# USB-C_Connector.net
KiCad netlist of a schematic drawn in Altium Designer
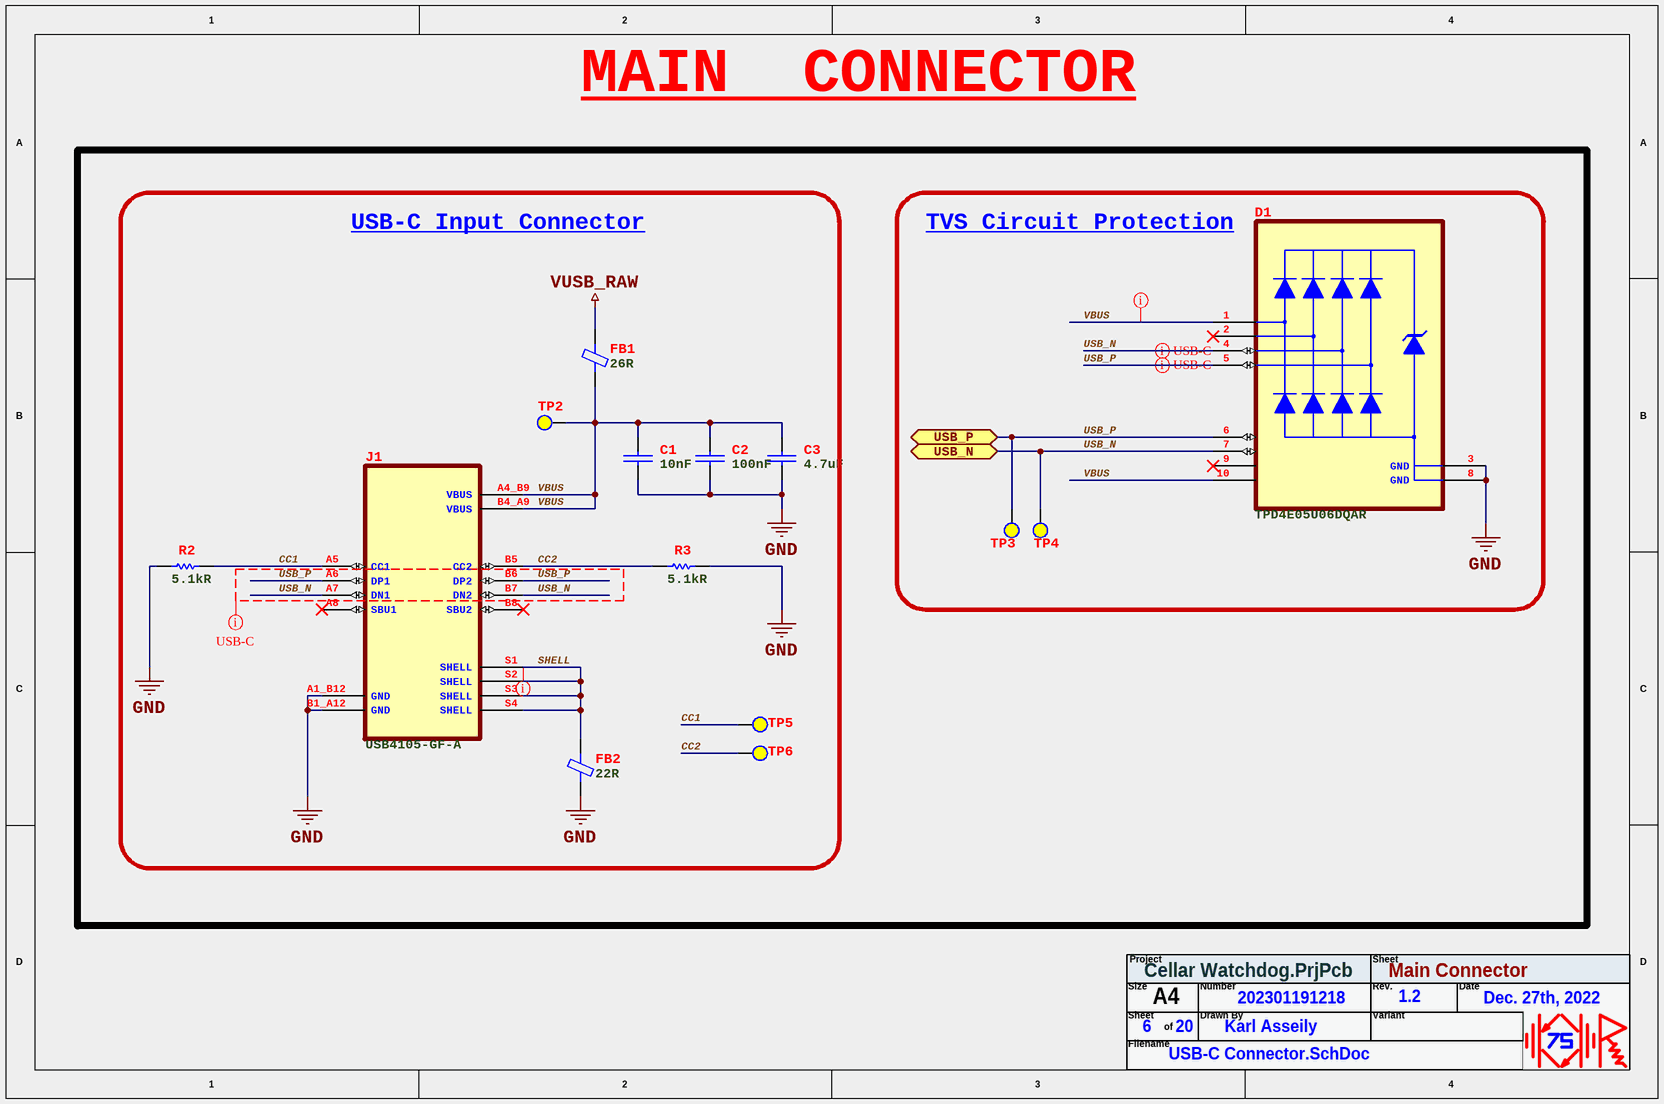
[diagram p0: USB-C Connector.SchDoc]

(export (version "E")
  (design (tool "Eeschema 10.0.6"))
  (components
    (comp (ref "C1")
      (value "10nF")
      (footprint "CAP_0603")
      (description "10000 pF ±10% 50V Ceramic Capacitor X7R 0603 (1608 Metric)")
      (fields
        (field (name "MANUFACTURER") "Yageo")
        (field (name "MANUFACTURER PART NUMBER") "CC0603KRX7R9BB103")
      )
      (libsource (lib "Cellar Watchdog") (part "CAP_10nF-50V-10%_0603"))
    )
    (comp (ref "C2")
      (value "100nF")
      (footprint "CAP_0603")
      (description "0.1 µF ±10% 50V Ceramic Capacitor X7R 0603 (1608 Metric)")
      (fields
        (field (name "MANUFACTURER") "Yageo")
        (field (name "MANUFACTURER PART NUMBER") "CC0603KRX7R9BB104")
      )
      (libsource (lib "Cellar Watchdog") (part "CAP_0.1uF-50V-10%_0603"))
    )
    (comp (ref "C3")
      (value "4.7uF")
      (footprint "CAP_0805")
      (description "4.7 µF ±10% 25V Ceramic Capacitor X7R 0805 (2012 Metric)")
      (fields
        (field (name "MANUFACTURER") "Yageo")
        (field (name "MANUFACTURER PART NUMBER") "CC0805KKX7R8BB475")
      )
      (libsource (lib "Cellar Watchdog") (part "CAP_4.7uF-25V-10%_0805"))
    )
    (comp (ref "D1")
      (value "TPD4E05U06DQAR")
      (footprint "DIO-T-A_10-USON")
      (description "14V Clamp 2.5A (8/20µs) Ipp Tvs Diode Surface Mount 10-USON (2.5x1)")
      (fields (field (name "MANUFACTURER") "Texas Instruments"))
      (libsource (lib "Cellar Watchdog") (part "DIO-T-A-UNI_6V-14V-2.5A_10-USON"))
    )
    (comp (ref "FB1")
      (value "26R")
      (footprint "FB_0603")
      (description "26 Ohms @ 100 MHz 1 Power Line Ferrite Bead 0603 (1608 Metric) 6A 7mOhm")
      (fields
        (field (name "MANUFACTURER") "Murata")
        (field (name "MANUFACTURER PART NUMBER") "BLM18SG260TZ1D")
      )
      (libsource (lib "Cellar Watchdog") (part "FB_26R-100MHz-6A_0603"))
    )
    (comp (ref "FB2")
      (value "22R")
      (footprint "FB_0603")
      (description "22 Ohms @ 100 MHz 1 Signal Line Ferrite Bead 0603 (1608 Metric) 500mA 350mOhm")
      (fields
        (field (name "MANUFACTURER") "Murata")
        (field (name "MANUFACTURER PART NUMBER") "BLM18BA220SN1D")
      )
      (libsource (lib "Cellar Watchdog") (part "FB_22R-100MHz-500mA_0603"))
    )
    (comp (ref "J1")
      (value "USB4105-GF-A")
      (footprint "CON-RCPT_USB2.0-Type-C_GCT_USB4105-GF-A")
      (fields (field (name "MANUFACTURER") "Global Connector Technology"))
      (libsource (lib "Cellar Watchdog") (part "CON-RCPT_USB2.0-Type-C_USB4105-GF-A"))
    )
    (comp (ref "R2")
      (value "5.1kR")
      (footprint "RES_0603")
      (description "5.1 kOhms ±1% 0.1W, 1/10W Chip Resistor 0603 (1608 Metric) Moisture Resistant Thick Film")
      (fields
        (field (name "MANUFACTURER") "Yageo")
        (field (name "MANUFACTURER PART NUMBER") "RC0603FR-075K1L")
      )
      (libsource (lib "Cellar Watchdog") (part "RES_5.1kR-100mW-1%_0603"))
    )
    (comp (ref "R3")
      (value "5.1kR")
      (footprint "RES_0603")
      (description "5.1 kOhms ±1% 0.1W, 1/10W Chip Resistor 0603 (1608 Metric) Moisture Resistant Thick Film")
      (fields
        (field (name "MANUFACTURER") "Yageo")
        (field (name "MANUFACTURER PART NUMBER") "RC0603FR-075K1L")
      )
      (libsource (lib "Cellar Watchdog") (part "RES_5.1kR-100mW-1%_0603"))
    )
    (comp (ref "TP2")
      (value "VBUS")
      (footprint "TEST POINT HOLE")
      (description "PCB Test Point")
      (libsource (lib "Cellar Watchdog") (part "Test Point"))
    )
    (comp (ref "TP3")
      (value "USB_P")
      (footprint "TEST POINT PAD")
      (description "PCB Test Point")
      (libsource (lib "Cellar Watchdog") (part "Test Point"))
    )
    (comp (ref "TP4")
      (value "USB_N")
      (footprint "TEST POINT PAD")
      (description "PCB Test Point")
      (libsource (lib "Cellar Watchdog") (part "Test Point"))
    )
    (comp (ref "TP5")
      (value "CC1")
      (footprint "TEST POINT PAD")
      (description "PCB Test Point")
      (libsource (lib "Cellar Watchdog") (part "Test Point"))
    )
    (comp (ref "TP6")
      (value "CC2")
      (footprint "TEST POINT PAD")
      (description "PCB Test Point")
      (libsource (lib "Cellar Watchdog") (part "Test Point"))
    )
  )
  (nets
    (net (code "1") (name "/CC1") (class "Default")
      (node (ref "J1") (pin "A5") (pinfunction "CC1_A5") (pintype "bidirectional"))
      (node (ref "R2") (pin "1") (pinfunction "1_1") (pintype "passive"))
      (node (ref "TP5") (pin "TP") (pinfunction "TP_TP") (pintype "passive"))
    )
    (net (code "2") (name "/CC2") (class "Default")
      (node (ref "J1") (pin "B5") (pinfunction "CC2_B5") (pintype "bidirectional"))
      (node (ref "R3") (pin "1") (pinfunction "1_1") (pintype "passive"))
      (node (ref "TP6") (pin "TP") (pinfunction "TP_TP") (pintype "passive"))
    )
    (net (code "3") (name "/SHELL") (class "Default")
      (node (ref "FB2") (pin "1") (pinfunction "1_1") (pintype "passive"))
      (node (ref "J1") (pin "S1") (pinfunction "SHELL_S1") (pintype "power_in"))
      (node (ref "J1") (pin "S2") (pinfunction "SHELL_S2") (pintype "power_in"))
      (node (ref "J1") (pin "S3") (pinfunction "SHELL_S3") (pintype "power_in"))
      (node (ref "J1") (pin "S4") (pinfunction "SHELL_S4") (pintype "power_in"))
    )
    (net (code "4") (name "/USB_N") (class "Default")
      (node (ref "D1") (pin "4") (pinfunction "D2+_4") (pintype "bidirectional"))
      (node (ref "D1") (pin "7") (pinfunction "NC_7") (pintype "bidirectional"))
      (node (ref "J1") (pin "A7") (pinfunction "DN1_A7") (pintype "bidirectional"))
      (node (ref "J1") (pin "B7") (pinfunction "DN2_B7") (pintype "bidirectional"))
      (node (ref "TP4") (pin "TP") (pinfunction "TP_TP") (pintype "passive"))
    )
    (net (code "5") (name "/USB_P") (class "Default")
      (node (ref "D1") (pin "5") (pinfunction "D2-_5") (pintype "bidirectional"))
      (node (ref "D1") (pin "6") (pinfunction "NC_6") (pintype "bidirectional"))
      (node (ref "J1") (pin "A6") (pinfunction "DP1_A6") (pintype "bidirectional"))
      (node (ref "J1") (pin "B6") (pinfunction "DP2_B6") (pintype "bidirectional"))
      (node (ref "TP3") (pin "TP") (pinfunction "TP_TP") (pintype "passive"))
    )
    (net (code "6") (name "/VBUS") (class "Default")
      (node (ref "C1") (pin "1") (pinfunction "1_1") (pintype "passive"))
      (node (ref "C2") (pin "1") (pinfunction "1_1") (pintype "passive"))
      (node (ref "C3") (pin "1") (pinfunction "1_1") (pintype "passive"))
      (node (ref "D1") (pin "1") (pinfunction "D1+_1") (pintype "power_in"))
      (node (ref "D1") (pin "10") (pinfunction "NC_10") (pintype "power_in"))
      (node (ref "FB1") (pin "1") (pinfunction "1_1") (pintype "passive"))
      (node (ref "J1") (pin "A4_B9") (pinfunction "VBUS_A4_B9") (pintype "power_in"))
      (node (ref "J1") (pin "B4_A9") (pinfunction "VBUS_B4_A9") (pintype "power_in"))
      (node (ref "TP2") (pin "TP") (pinfunction "TP_TP") (pintype "passive"))
    )
    (net (code "7") (name "GND") (class "Default")
      (node (ref "C1") (pin "2") (pinfunction "2_2") (pintype "passive"))
      (node (ref "C2") (pin "2") (pinfunction "2_2") (pintype "passive"))
      (node (ref "C3") (pin "2") (pinfunction "2_2") (pintype "passive"))
      (node (ref "D1") (pin "3") (pinfunction "GND_3") (pintype "power_in"))
      (node (ref "D1") (pin "8") (pinfunction "GND_8") (pintype "power_in"))
      (node (ref "FB2") (pin "2") (pinfunction "2_2") (pintype "passive"))
      (node (ref "J1") (pin "A1_B12") (pinfunction "GND_A1_B12") (pintype "power_in"))
      (node (ref "J1") (pin "B1_A12") (pinfunction "GND_B1_A12") (pintype "power_in"))
      (node (ref "R2") (pin "2") (pinfunction "2_2") (pintype "passive"))
      (node (ref "R3") (pin "2") (pinfunction "2_2") (pintype "passive"))
    )
    (net (code "8") (name "VUSB_RAW") (class "Default")
      (node (ref "FB1") (pin "2") (pinfunction "2_2") (pintype "passive"))
    )
    (net (code "9") (name "unconnected-(D1-D1--Pad2)") (class "Default")
      (node (ref "D1") (pin "2") (pinfunction "D1-_2") (pintype "passive+no_connect"))
    )
    (net (code "10") (name "unconnected-(D1-NC-Pad9)") (class "Default")
      (node (ref "D1") (pin "9") (pinfunction "NC_9") (pintype "passive+no_connect"))
    )
    (net (code "11") (name "unconnected-(J1-SBU1-PadA8)") (class "Default")
      (node (ref "J1") (pin "A8") (pinfunction "SBU1_A8") (pintype "bidirectional+no_connect"))
    )
    (net (code "12") (name "unconnected-(J1-SBU2-PadB8)") (class "Default")
      (node (ref "J1") (pin "B8") (pinfunction "SBU2_B8") (pintype "bidirectional+no_connect"))
    )
  )
)
